# mezza.net
KiCad netlist of a schematic drawn in EAGLE
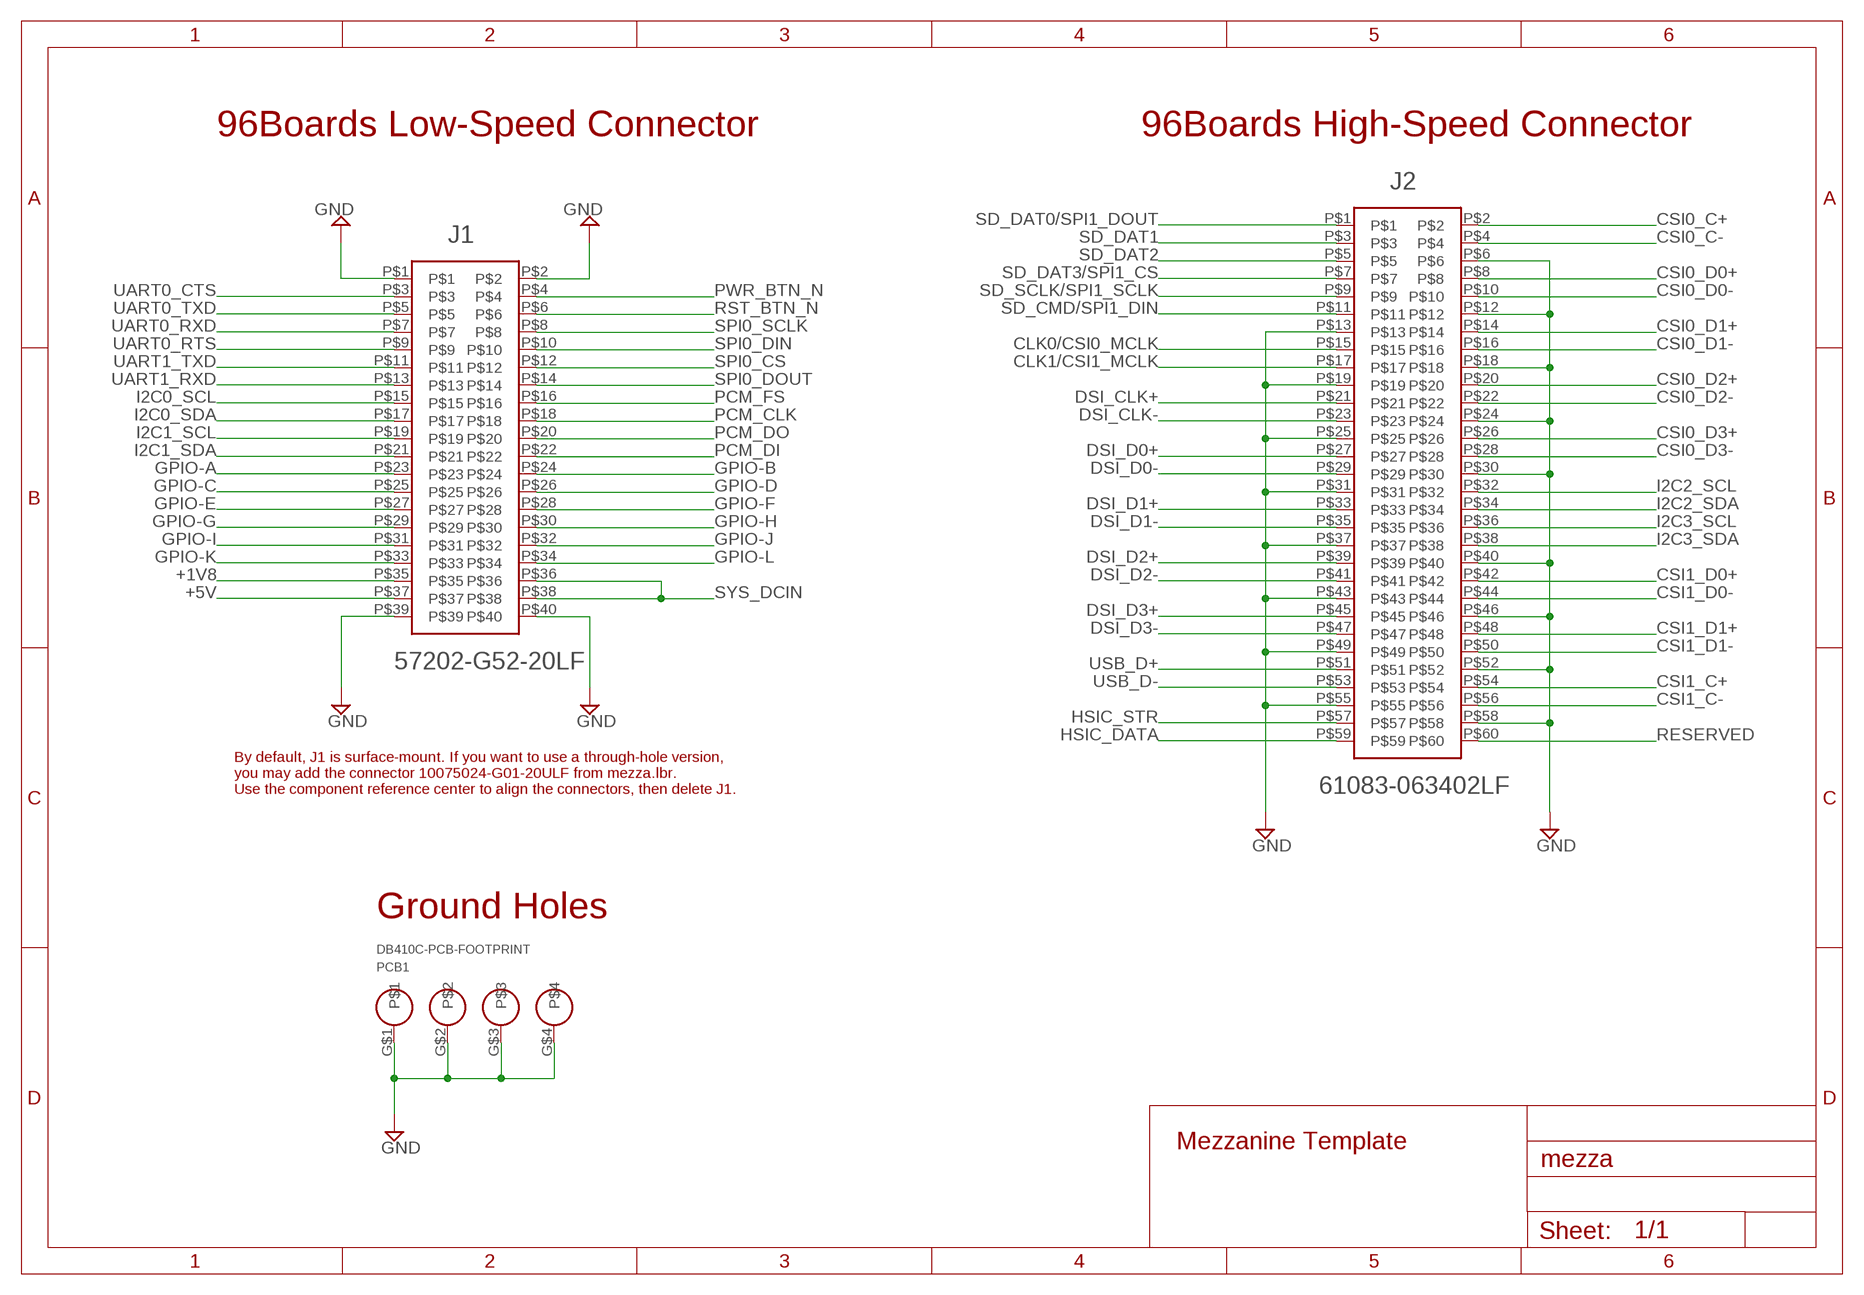
[diagram p0: schematic, sheet 1]

(export (version "E")
  (design (tool "Eeschema 10.0.6"))
  (components
    (comp (ref "J1")
      (value "57202-G52-20LF")
      (footprint "eagle-import:57202-G52-20LF")
      (libsource (lib "eagle-import") (part "57202-G52-20LF"))
    )
    (comp (ref "J2")
      (value "61083-063402LF")
      (footprint "eagle-import:61083-063402LF")
      (libsource (lib "eagle-import") (part "61083-063402LF"))
    )
    (comp (ref "PCB1")
      (value "DB410C-PCB-FOOTPRINT")
      (footprint "eagle-import:DRAGONBOARD410C")
      (libsource (lib "eagle-import") (part "DB410C-PCB-FOOTPRINT"))
    )
  )
  (nets
    (net (code "1") (name "/+1V8") (class "Default")
      (node (ref "J1") (pin "P$35") (pinfunction "P$35_P$35") (pintype "bidirectional"))
    )
    (net (code "2") (name "/+5V") (class "Default")
      (node (ref "J1") (pin "P$37") (pinfunction "P$37_P$37") (pintype "bidirectional"))
    )
    (net (code "3") (name "/CLK0{slash}CSI0_MCLK") (class "Default")
      (node (ref "J2") (pin "P$15") (pinfunction "P$15_P$15") (pintype "bidirectional"))
    )
    (net (code "4") (name "/CLK1{slash}CSI1_MCLK") (class "Default")
      (node (ref "J2") (pin "P$17") (pinfunction "P$17_P$17") (pintype "bidirectional"))
    )
    (net (code "5") (name "/CSI0_C+") (class "Default")
      (node (ref "J2") (pin "P$2") (pinfunction "P$2_P$2") (pintype "bidirectional"))
    )
    (net (code "6") (name "/CSI0_C-") (class "Default")
      (node (ref "J2") (pin "P$4") (pinfunction "P$4_P$4") (pintype "bidirectional"))
    )
    (net (code "7") (name "/CSI0_D0+") (class "Default")
      (node (ref "J2") (pin "P$8") (pinfunction "P$8_P$8") (pintype "bidirectional"))
    )
    (net (code "8") (name "/CSI0_D0-") (class "Default")
      (node (ref "J2") (pin "P$10") (pinfunction "P$10_P$10") (pintype "bidirectional"))
    )
    (net (code "9") (name "/CSI0_D1+") (class "Default")
      (node (ref "J2") (pin "P$14") (pinfunction "P$14_P$14") (pintype "bidirectional"))
    )
    (net (code "10") (name "/CSI0_D1-") (class "Default")
      (node (ref "J2") (pin "P$16") (pinfunction "P$16_P$16") (pintype "bidirectional"))
    )
    (net (code "11") (name "/CSI0_D2+") (class "Default")
      (node (ref "J2") (pin "P$20") (pinfunction "P$20_P$20") (pintype "bidirectional"))
    )
    (net (code "12") (name "/CSI0_D2-") (class "Default")
      (node (ref "J2") (pin "P$22") (pinfunction "P$22_P$22") (pintype "bidirectional"))
    )
    (net (code "13") (name "/CSI0_D3+") (class "Default")
      (node (ref "J2") (pin "P$26") (pinfunction "P$26_P$26") (pintype "bidirectional"))
    )
    (net (code "14") (name "/CSI0_D3-") (class "Default")
      (node (ref "J2") (pin "P$28") (pinfunction "P$28_P$28") (pintype "bidirectional"))
    )
    (net (code "15") (name "/CSI1_C+") (class "Default")
      (node (ref "J2") (pin "P$54") (pinfunction "P$54_P$54") (pintype "bidirectional"))
    )
    (net (code "16") (name "/CSI1_C-") (class "Default")
      (node (ref "J2") (pin "P$56") (pinfunction "P$56_P$56") (pintype "bidirectional"))
    )
    (net (code "17") (name "/CSI1_D0+") (class "Default")
      (node (ref "J2") (pin "P$42") (pinfunction "P$42_P$42") (pintype "bidirectional"))
    )
    (net (code "18") (name "/CSI1_D0-") (class "Default")
      (node (ref "J2") (pin "P$44") (pinfunction "P$44_P$44") (pintype "bidirectional"))
    )
    (net (code "19") (name "/CSI1_D1+") (class "Default")
      (node (ref "J2") (pin "P$48") (pinfunction "P$48_P$48") (pintype "bidirectional"))
    )
    (net (code "20") (name "/CSI1_D1-") (class "Default")
      (node (ref "J2") (pin "P$50") (pinfunction "P$50_P$50") (pintype "bidirectional"))
    )
    (net (code "21") (name "/DSI_CLK+") (class "Default")
      (node (ref "J2") (pin "P$21") (pinfunction "P$21_P$21") (pintype "bidirectional"))
    )
    (net (code "22") (name "/DSI_CLK-") (class "Default")
      (node (ref "J2") (pin "P$23") (pinfunction "P$23_P$23") (pintype "bidirectional"))
    )
    (net (code "23") (name "/DSI_D0+") (class "Default")
      (node (ref "J2") (pin "P$27") (pinfunction "P$27_P$27") (pintype "bidirectional"))
    )
    (net (code "24") (name "/DSI_D0-") (class "Default")
      (node (ref "J2") (pin "P$29") (pinfunction "P$29_P$29") (pintype "bidirectional"))
    )
    (net (code "25") (name "/DSI_D1+") (class "Default")
      (node (ref "J2") (pin "P$33") (pinfunction "P$33_P$33") (pintype "bidirectional"))
    )
    (net (code "26") (name "/DSI_D1-") (class "Default")
      (node (ref "J2") (pin "P$35") (pinfunction "P$35_P$35") (pintype "bidirectional"))
    )
    (net (code "27") (name "/DSI_D2+") (class "Default")
      (node (ref "J2") (pin "P$39") (pinfunction "P$39_P$39") (pintype "bidirectional"))
    )
    (net (code "28") (name "/DSI_D2-") (class "Default")
      (node (ref "J2") (pin "P$41") (pinfunction "P$41_P$41") (pintype "bidirectional"))
    )
    (net (code "29") (name "/DSI_D3+") (class "Default")
      (node (ref "J2") (pin "P$45") (pinfunction "P$45_P$45") (pintype "bidirectional"))
    )
    (net (code "30") (name "/DSI_D3-") (class "Default")
      (node (ref "J2") (pin "P$47") (pinfunction "P$47_P$47") (pintype "bidirectional"))
    )
    (net (code "31") (name "/GPIO-A") (class "Default")
      (node (ref "J1") (pin "P$23") (pinfunction "P$23_P$23") (pintype "bidirectional"))
    )
    (net (code "32") (name "/GPIO-B") (class "Default")
      (node (ref "J1") (pin "P$24") (pinfunction "P$24_P$24") (pintype "bidirectional"))
    )
    (net (code "33") (name "/GPIO-C") (class "Default")
      (node (ref "J1") (pin "P$25") (pinfunction "P$25_P$25") (pintype "bidirectional"))
    )
    (net (code "34") (name "/GPIO-D") (class "Default")
      (node (ref "J1") (pin "P$26") (pinfunction "P$26_P$26") (pintype "bidirectional"))
    )
    (net (code "35") (name "/GPIO-E") (class "Default")
      (node (ref "J1") (pin "P$27") (pinfunction "P$27_P$27") (pintype "bidirectional"))
    )
    (net (code "36") (name "/GPIO-F") (class "Default")
      (node (ref "J1") (pin "P$28") (pinfunction "P$28_P$28") (pintype "bidirectional"))
    )
    (net (code "37") (name "/GPIO-G") (class "Default")
      (node (ref "J1") (pin "P$29") (pinfunction "P$29_P$29") (pintype "bidirectional"))
    )
    (net (code "38") (name "/GPIO-H") (class "Default")
      (node (ref "J1") (pin "P$30") (pinfunction "P$30_P$30") (pintype "bidirectional"))
    )
    (net (code "39") (name "/GPIO-I") (class "Default")
      (node (ref "J1") (pin "P$31") (pinfunction "P$31_P$31") (pintype "bidirectional"))
    )
    (net (code "40") (name "/GPIO-J") (class "Default")
      (node (ref "J1") (pin "P$32") (pinfunction "P$32_P$32") (pintype "bidirectional"))
    )
    (net (code "41") (name "/GPIO-K") (class "Default")
      (node (ref "J1") (pin "P$33") (pinfunction "P$33_P$33") (pintype "bidirectional"))
    )
    (net (code "42") (name "/GPIO-L") (class "Default")
      (node (ref "J1") (pin "P$34") (pinfunction "P$34_P$34") (pintype "bidirectional"))
    )
    (net (code "43") (name "/HSIC_DATA") (class "Default")
      (node (ref "J2") (pin "P$59") (pinfunction "P$59_P$59") (pintype "bidirectional"))
    )
    (net (code "44") (name "/HSIC_STR") (class "Default")
      (node (ref "J2") (pin "P$57") (pinfunction "P$57_P$57") (pintype "bidirectional"))
    )
    (net (code "45") (name "/I2C0_SCL") (class "Default")
      (node (ref "J1") (pin "P$15") (pinfunction "P$15_P$15") (pintype "bidirectional"))
    )
    (net (code "46") (name "/I2C0_SDA") (class "Default")
      (node (ref "J1") (pin "P$17") (pinfunction "P$17_P$17") (pintype "bidirectional"))
    )
    (net (code "47") (name "/I2C1_SCL") (class "Default")
      (node (ref "J1") (pin "P$19") (pinfunction "P$19_P$19") (pintype "bidirectional"))
    )
    (net (code "48") (name "/I2C1_SDA") (class "Default")
      (node (ref "J1") (pin "P$21") (pinfunction "P$21_P$21") (pintype "bidirectional"))
    )
    (net (code "49") (name "/I2C2_SCL") (class "Default")
      (node (ref "J2") (pin "P$32") (pinfunction "P$32_P$32") (pintype "bidirectional"))
    )
    (net (code "50") (name "/I2C2_SDA") (class "Default")
      (node (ref "J2") (pin "P$34") (pinfunction "P$34_P$34") (pintype "bidirectional"))
    )
    (net (code "51") (name "/I2C3_SCL") (class "Default")
      (node (ref "J2") (pin "P$36") (pinfunction "P$36_P$36") (pintype "bidirectional"))
    )
    (net (code "52") (name "/I2C3_SDA") (class "Default")
      (node (ref "J2") (pin "P$38") (pinfunction "P$38_P$38") (pintype "bidirectional"))
    )
    (net (code "53") (name "/PCM_CLK") (class "Default")
      (node (ref "J1") (pin "P$18") (pinfunction "P$18_P$18") (pintype "bidirectional"))
    )
    (net (code "54") (name "/PCM_DI") (class "Default")
      (node (ref "J1") (pin "P$22") (pinfunction "P$22_P$22") (pintype "bidirectional"))
    )
    (net (code "55") (name "/PCM_DO") (class "Default")
      (node (ref "J1") (pin "P$20") (pinfunction "P$20_P$20") (pintype "bidirectional"))
    )
    (net (code "56") (name "/PCM_FS") (class "Default")
      (node (ref "J1") (pin "P$16") (pinfunction "P$16_P$16") (pintype "bidirectional"))
    )
    (net (code "57") (name "/PWR_BTN_N") (class "Default")
      (node (ref "J1") (pin "P$4") (pinfunction "P$4_P$4") (pintype "bidirectional"))
    )
    (net (code "58") (name "/RESERVED") (class "Default")
      (node (ref "J2") (pin "P$60") (pinfunction "P$60_P$60") (pintype "bidirectional"))
    )
    (net (code "59") (name "/RST_BTN_N") (class "Default")
      (node (ref "J1") (pin "P$6") (pinfunction "P$6_P$6") (pintype "bidirectional"))
    )
    (net (code "60") (name "/SD_CMD{slash}SPI1_DIN") (class "Default")
      (node (ref "J2") (pin "P$11") (pinfunction "P$11_P$11") (pintype "bidirectional"))
    )
    (net (code "61") (name "/SD_DAT0{slash}SPI1_DOUT") (class "Default")
      (node (ref "J2") (pin "P$1") (pinfunction "P$1_P$1") (pintype "bidirectional"))
    )
    (net (code "62") (name "/SD_DAT1") (class "Default")
      (node (ref "J2") (pin "P$3") (pinfunction "P$3_P$3") (pintype "bidirectional"))
    )
    (net (code "63") (name "/SD_DAT2") (class "Default")
      (node (ref "J2") (pin "P$5") (pinfunction "P$5_P$5") (pintype "bidirectional"))
    )
    (net (code "64") (name "/SD_DAT3{slash}SPI1_CS") (class "Default")
      (node (ref "J2") (pin "P$7") (pinfunction "P$7_P$7") (pintype "bidirectional"))
    )
    (net (code "65") (name "/SD_SCLK{slash}SPI1_SCLK") (class "Default")
      (node (ref "J2") (pin "P$9") (pinfunction "P$9_P$9") (pintype "bidirectional"))
    )
    (net (code "66") (name "/SPI0_CS") (class "Default")
      (node (ref "J1") (pin "P$12") (pinfunction "P$12_P$12") (pintype "bidirectional"))
    )
    (net (code "67") (name "/SPI0_DIN") (class "Default")
      (node (ref "J1") (pin "P$10") (pinfunction "P$10_P$10") (pintype "bidirectional"))
    )
    (net (code "68") (name "/SPI0_DOUT") (class "Default")
      (node (ref "J1") (pin "P$14") (pinfunction "P$14_P$14") (pintype "bidirectional"))
    )
    (net (code "69") (name "/SPI0_SCLK") (class "Default")
      (node (ref "J1") (pin "P$8") (pinfunction "P$8_P$8") (pintype "bidirectional"))
    )
    (net (code "70") (name "/SYS_DCIN") (class "Default")
      (node (ref "J1") (pin "P$36") (pinfunction "P$36_P$36") (pintype "bidirectional"))
      (node (ref "J1") (pin "P$38") (pinfunction "P$38_P$38") (pintype "bidirectional"))
    )
    (net (code "71") (name "/UART0_CTS") (class "Default")
      (node (ref "J1") (pin "P$3") (pinfunction "P$3_P$3") (pintype "bidirectional"))
    )
    (net (code "72") (name "/UART0_RTS") (class "Default")
      (node (ref "J1") (pin "P$9") (pinfunction "P$9_P$9") (pintype "bidirectional"))
    )
    (net (code "73") (name "/UART0_RXD") (class "Default")
      (node (ref "J1") (pin "P$7") (pinfunction "P$7_P$7") (pintype "bidirectional"))
    )
    (net (code "74") (name "/UART0_TXD") (class "Default")
      (node (ref "J1") (pin "P$5") (pinfunction "P$5_P$5") (pintype "bidirectional"))
    )
    (net (code "75") (name "/UART1_RXD") (class "Default")
      (node (ref "J1") (pin "P$13") (pinfunction "P$13_P$13") (pintype "bidirectional"))
    )
    (net (code "76") (name "/UART1_TXD") (class "Default")
      (node (ref "J1") (pin "P$11") (pinfunction "P$11_P$11") (pintype "bidirectional"))
    )
    (net (code "77") (name "/USB_D+") (class "Default")
      (node (ref "J2") (pin "P$51") (pinfunction "P$51_P$51") (pintype "bidirectional"))
    )
    (net (code "78") (name "/USB_D-") (class "Default")
      (node (ref "J2") (pin "P$53") (pinfunction "P$53_P$53") (pintype "bidirectional"))
    )
    (net (code "79") (name "GND") (class "Default")
      (node (ref "J1") (pin "P$1") (pinfunction "P$1_P$1") (pintype "bidirectional"))
      (node (ref "J1") (pin "P$2") (pinfunction "P$2_P$2") (pintype "bidirectional"))
      (node (ref "J1") (pin "P$39") (pinfunction "P$39_P$39") (pintype "bidirectional"))
      (node (ref "J1") (pin "P$40") (pinfunction "P$40_P$40") (pintype "bidirectional"))
      (node (ref "J2") (pin "P$12") (pinfunction "P$12_P$12") (pintype "bidirectional"))
      (node (ref "J2") (pin "P$13") (pinfunction "P$13_P$13") (pintype "bidirectional"))
      (node (ref "J2") (pin "P$18") (pinfunction "P$18_P$18") (pintype "bidirectional"))
      (node (ref "J2") (pin "P$19") (pinfunction "P$19_P$19") (pintype "bidirectional"))
      (node (ref "J2") (pin "P$24") (pinfunction "P$24_P$24") (pintype "bidirectional"))
      (node (ref "J2") (pin "P$25") (pinfunction "P$25_P$25") (pintype "bidirectional"))
      (node (ref "J2") (pin "P$30") (pinfunction "P$30_P$30") (pintype "bidirectional"))
      (node (ref "J2") (pin "P$31") (pinfunction "P$31_P$31") (pintype "bidirectional"))
      (node (ref "J2") (pin "P$37") (pinfunction "P$37_P$37") (pintype "bidirectional"))
      (node (ref "J2") (pin "P$40") (pinfunction "P$40_P$40") (pintype "bidirectional"))
      (node (ref "J2") (pin "P$43") (pinfunction "P$43_P$43") (pintype "bidirectional"))
      (node (ref "J2") (pin "P$46") (pinfunction "P$46_P$46") (pintype "bidirectional"))
      (node (ref "J2") (pin "P$49") (pinfunction "P$49_P$49") (pintype "bidirectional"))
      (node (ref "J2") (pin "P$52") (pinfunction "P$52_P$52") (pintype "bidirectional"))
      (node (ref "J2") (pin "P$55") (pinfunction "P$55_P$55") (pintype "bidirectional"))
      (node (ref "J2") (pin "P$58") (pinfunction "P$58_P$58") (pintype "bidirectional"))
      (node (ref "J2") (pin "P$6") (pinfunction "P$6_P$6") (pintype "bidirectional"))
      (node (ref "PCB1") (pin "G$1") (pinfunction "P$1_G$1") (pintype "bidirectional"))
      (node (ref "PCB1") (pin "G$2") (pinfunction "P$2_G$2") (pintype "bidirectional"))
      (node (ref "PCB1") (pin "G$3") (pinfunction "P$3_G$3") (pintype "bidirectional"))
      (node (ref "PCB1") (pin "G$4") (pinfunction "P$4_G$4") (pintype "bidirectional"))
    )
  )
)
